# UV_lamp.net
KiCad netlist of a schematic drawn in EAGLE
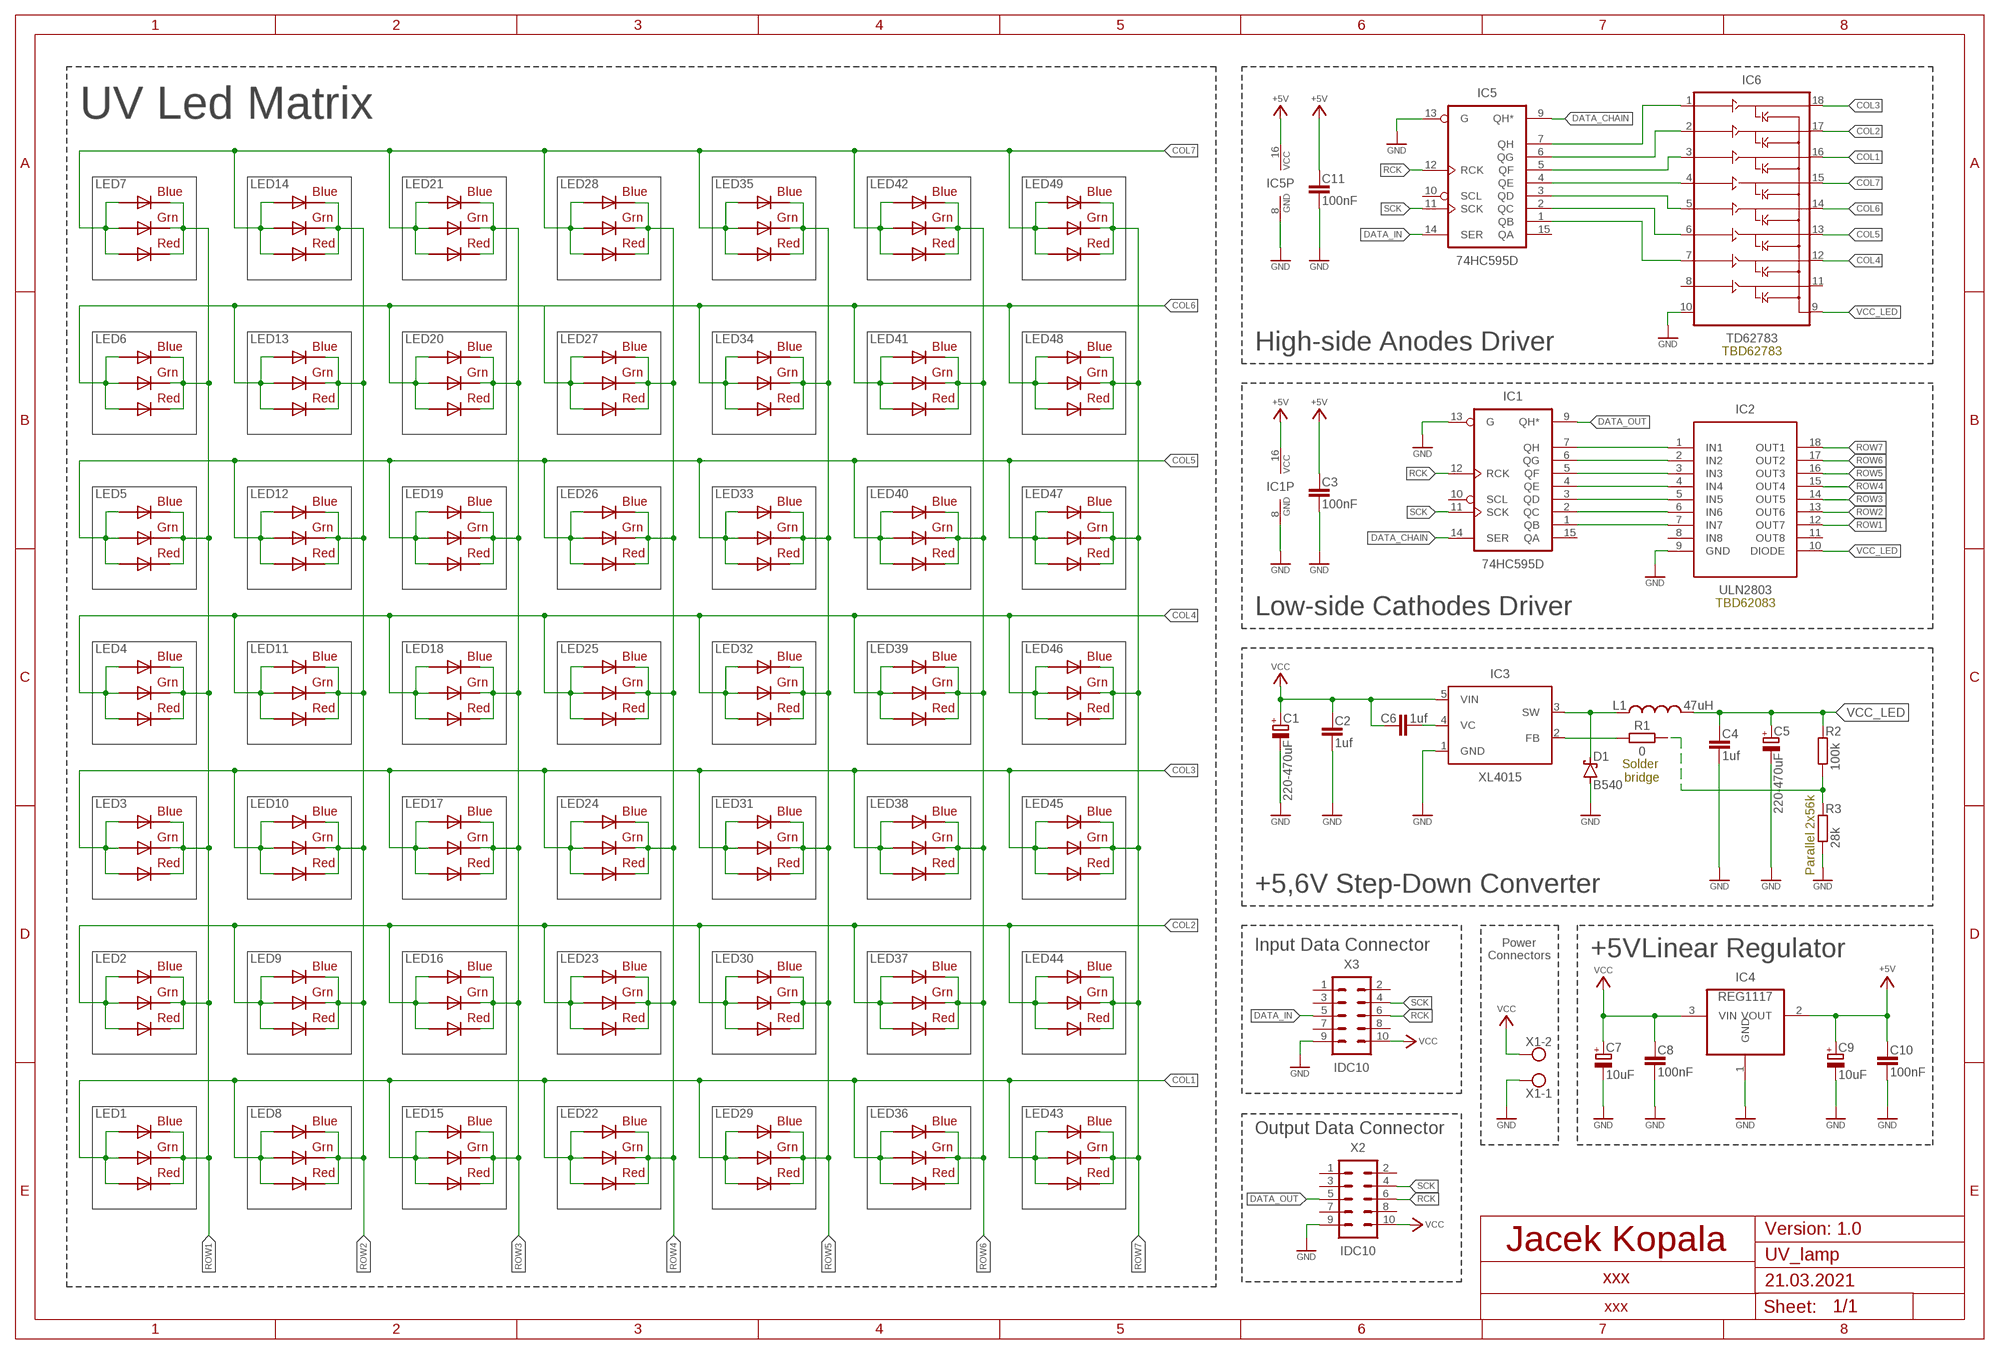
[diagram p0: schematic, sheet 1]

(export (version "E")
  (design (tool "Eeschema 10.0.6"))
  (components
    (comp (ref "C1")
      (value "220-470uF")
      (footprint "eagle-import:140CLH-1010")
      (libsource (lib "eagle-import") (part "CPOL-EU140CLH-1010"))
    )
    (comp (ref "C2")
      (value "1uf")
      (footprint "eagle-import:C0805")
      (fields (field (name "SPICEPREFIX") "C"))
      (libsource (lib "eagle-import") (part "C-EUC0805"))
    )
    (comp (ref "C3")
      (value "100nF")
      (footprint "eagle-import:C0805")
      (libsource (lib "eagle-import") (part "rcl_334_C-EUC0805"))
    )
    (comp (ref "C4")
      (value "1uf")
      (footprint "eagle-import:C0805")
      (fields (field (name "SPICEPREFIX") "C"))
      (libsource (lib "eagle-import") (part "C-EUC0805"))
    )
    (comp (ref "C5")
      (value "220-470uF")
      (footprint "eagle-import:140CLH-1010")
      (libsource (lib "eagle-import") (part "CPOL-EU140CLH-1010"))
    )
    (comp (ref "C6")
      (value "1uf")
      (footprint "eagle-import:C0805")
      (fields (field (name "SPICEPREFIX") "C"))
      (libsource (lib "eagle-import") (part "C-EUC0805"))
    )
    (comp (ref "C7")
      (value "10uF")
      (footprint "eagle-import:153CLV-0405")
      (libsource (lib "eagle-import") (part "CPOL-EU153CLV-0405"))
    )
    (comp (ref "C8")
      (value "100nF")
      (footprint "eagle-import:C0805")
      (fields (field (name "SPICEPREFIX") "C"))
      (libsource (lib "eagle-import") (part "C-EUC0805"))
    )
    (comp (ref "C9")
      (value "10uF")
      (footprint "eagle-import:153CLV-0405")
      (libsource (lib "eagle-import") (part "CPOL-EU153CLV-0405"))
    )
    (comp (ref "C10")
      (value "100nF")
      (footprint "eagle-import:C0805")
      (fields (field (name "SPICEPREFIX") "C"))
      (libsource (lib "eagle-import") (part "C-EUC0805"))
    )
    (comp (ref "C11")
      (value "100nF")
      (footprint "eagle-import:C0805")
      (libsource (lib "eagle-import") (part "rcl_334_C-EUC0805"))
    )
    (comp (ref "D1")
      (value "B540")
      (footprint "eagle-import:SMC")
      (libsource (lib "eagle-import") (part "MBRS30T34"))
    )
    (comp (ref "IC1")
      (value "74HC595D")
      (footprint "eagle-import:SO16")
      (libsource (lib "eagle-import") (part "74595DHC"))
    )
    (comp (ref "IC2")
      (value "ULN2803")
      (footprint "eagle-import:SO18L")
      (libsource (lib "eagle-import") (part "ULN2803"))
    )
    (comp (ref "IC3")
      (value "XL4015")
      (footprint "eagle-import:TO263-5")
      (libsource (lib "eagle-import") (part "XL4015"))
    )
    (comp (ref "IC4")
      (value "REG1117")
      (footprint "eagle-import:SOT223")
      (libsource (lib "eagle-import") (part "REG1117"))
    )
    (comp (ref "IC5")
      (value "74HC595D")
      (footprint "eagle-import:SO16")
      (libsource (lib "eagle-import") (part "74595DHC"))
    )
    (comp (ref "IC6")
      (value "TD62783")
      (footprint "eagle-import:SO-18L")
      (libsource (lib "eagle-import") (part "IC_TD62783-SO-18W"))
    )
    (comp (ref "L1")
      (value "47uH")
      (footprint "eagle-import:TJ5-U1")
      (libsource (lib "eagle-import") (part "L-USTJ5-U1"))
    )
    (comp (ref "LED1")
      (value "RGBLED5050")
      (footprint "eagle-import:RGBLED5050")
      (libsource (lib "eagle-import") (part "RGBLED5050"))
    )
    (comp (ref "LED2")
      (value "RGBLED5050")
      (footprint "eagle-import:RGBLED5050")
      (libsource (lib "eagle-import") (part "RGBLED5050"))
    )
    (comp (ref "LED3")
      (value "RGBLED5050")
      (footprint "eagle-import:RGBLED5050")
      (libsource (lib "eagle-import") (part "RGBLED5050"))
    )
    (comp (ref "LED4")
      (value "RGBLED5050")
      (footprint "eagle-import:RGBLED5050")
      (libsource (lib "eagle-import") (part "RGBLED5050"))
    )
    (comp (ref "LED5")
      (value "RGBLED5050")
      (footprint "eagle-import:RGBLED5050")
      (libsource (lib "eagle-import") (part "RGBLED5050"))
    )
    (comp (ref "LED6")
      (value "RGBLED5050")
      (footprint "eagle-import:RGBLED5050")
      (libsource (lib "eagle-import") (part "RGBLED5050"))
    )
    (comp (ref "LED7")
      (value "RGBLED5050")
      (footprint "eagle-import:RGBLED5050")
      (libsource (lib "eagle-import") (part "RGBLED5050"))
    )
    (comp (ref "LED8")
      (value "RGBLED5050")
      (footprint "eagle-import:RGBLED5050")
      (libsource (lib "eagle-import") (part "RGBLED5050"))
    )
    (comp (ref "LED9")
      (value "RGBLED5050")
      (footprint "eagle-import:RGBLED5050")
      (libsource (lib "eagle-import") (part "RGBLED5050"))
    )
    (comp (ref "LED10")
      (value "RGBLED5050")
      (footprint "eagle-import:RGBLED5050")
      (libsource (lib "eagle-import") (part "RGBLED5050"))
    )
    (comp (ref "LED11")
      (value "RGBLED5050")
      (footprint "eagle-import:RGBLED5050")
      (libsource (lib "eagle-import") (part "RGBLED5050"))
    )
    (comp (ref "LED12")
      (value "RGBLED5050")
      (footprint "eagle-import:RGBLED5050")
      (libsource (lib "eagle-import") (part "RGBLED5050"))
    )
    (comp (ref "LED13")
      (value "RGBLED5050")
      (footprint "eagle-import:RGBLED5050")
      (libsource (lib "eagle-import") (part "RGBLED5050"))
    )
    (comp (ref "LED14")
      (value "RGBLED5050")
      (footprint "eagle-import:RGBLED5050")
      (libsource (lib "eagle-import") (part "RGBLED5050"))
    )
    (comp (ref "LED15")
      (value "RGBLED5050")
      (footprint "eagle-import:RGBLED5050")
      (libsource (lib "eagle-import") (part "RGBLED5050"))
    )
    (comp (ref "LED16")
      (value "RGBLED5050")
      (footprint "eagle-import:RGBLED5050")
      (libsource (lib "eagle-import") (part "RGBLED5050"))
    )
    (comp (ref "LED17")
      (value "RGBLED5050")
      (footprint "eagle-import:RGBLED5050")
      (libsource (lib "eagle-import") (part "RGBLED5050"))
    )
    (comp (ref "LED18")
      (value "RGBLED5050")
      (footprint "eagle-import:RGBLED5050")
      (libsource (lib "eagle-import") (part "RGBLED5050"))
    )
    (comp (ref "LED19")
      (value "RGBLED5050")
      (footprint "eagle-import:RGBLED5050")
      (libsource (lib "eagle-import") (part "RGBLED5050"))
    )
    (comp (ref "LED20")
      (value "RGBLED5050")
      (footprint "eagle-import:RGBLED5050")
      (libsource (lib "eagle-import") (part "RGBLED5050"))
    )
    (comp (ref "LED21")
      (value "RGBLED5050")
      (footprint "eagle-import:RGBLED5050")
      (libsource (lib "eagle-import") (part "RGBLED5050"))
    )
    (comp (ref "LED22")
      (value "RGBLED5050")
      (footprint "eagle-import:RGBLED5050")
      (libsource (lib "eagle-import") (part "RGBLED5050"))
    )
    (comp (ref "LED23")
      (value "RGBLED5050")
      (footprint "eagle-import:RGBLED5050")
      (libsource (lib "eagle-import") (part "RGBLED5050"))
    )
    (comp (ref "LED24")
      (value "RGBLED5050")
      (footprint "eagle-import:RGBLED5050")
      (libsource (lib "eagle-import") (part "RGBLED5050"))
    )
    (comp (ref "LED25")
      (value "RGBLED5050")
      (footprint "eagle-import:RGBLED5050")
      (libsource (lib "eagle-import") (part "RGBLED5050"))
    )
    (comp (ref "LED26")
      (value "RGBLED5050")
      (footprint "eagle-import:RGBLED5050")
      (libsource (lib "eagle-import") (part "RGBLED5050"))
    )
    (comp (ref "LED27")
      (value "RGBLED5050")
      (footprint "eagle-import:RGBLED5050")
      (libsource (lib "eagle-import") (part "RGBLED5050"))
    )
    (comp (ref "LED28")
      (value "RGBLED5050")
      (footprint "eagle-import:RGBLED5050")
      (libsource (lib "eagle-import") (part "RGBLED5050"))
    )
    (comp (ref "LED29")
      (value "RGBLED5050")
      (footprint "eagle-import:RGBLED5050")
      (libsource (lib "eagle-import") (part "RGBLED5050"))
    )
    (comp (ref "LED30")
      (value "RGBLED5050")
      (footprint "eagle-import:RGBLED5050")
      (libsource (lib "eagle-import") (part "RGBLED5050"))
    )
    (comp (ref "LED31")
      (value "RGBLED5050")
      (footprint "eagle-import:RGBLED5050")
      (libsource (lib "eagle-import") (part "RGBLED5050"))
    )
    (comp (ref "LED32")
      (value "RGBLED5050")
      (footprint "eagle-import:RGBLED5050")
      (libsource (lib "eagle-import") (part "RGBLED5050"))
    )
    (comp (ref "LED33")
      (value "RGBLED5050")
      (footprint "eagle-import:RGBLED5050")
      (libsource (lib "eagle-import") (part "RGBLED5050"))
    )
    (comp (ref "LED34")
      (value "RGBLED5050")
      (footprint "eagle-import:RGBLED5050")
      (libsource (lib "eagle-import") (part "RGBLED5050"))
    )
    (comp (ref "LED35")
      (value "RGBLED5050")
      (footprint "eagle-import:RGBLED5050")
      (libsource (lib "eagle-import") (part "RGBLED5050"))
    )
    (comp (ref "LED36")
      (value "RGBLED5050")
      (footprint "eagle-import:RGBLED5050")
      (libsource (lib "eagle-import") (part "RGBLED5050"))
    )
    (comp (ref "LED37")
      (value "RGBLED5050")
      (footprint "eagle-import:RGBLED5050")
      (libsource (lib "eagle-import") (part "RGBLED5050"))
    )
    (comp (ref "LED38")
      (value "RGBLED5050")
      (footprint "eagle-import:RGBLED5050")
      (libsource (lib "eagle-import") (part "RGBLED5050"))
    )
    (comp (ref "LED39")
      (value "RGBLED5050")
      (footprint "eagle-import:RGBLED5050")
      (libsource (lib "eagle-import") (part "RGBLED5050"))
    )
    (comp (ref "LED40")
      (value "RGBLED5050")
      (footprint "eagle-import:RGBLED5050")
      (libsource (lib "eagle-import") (part "RGBLED5050"))
    )
    (comp (ref "LED41")
      (value "RGBLED5050")
      (footprint "eagle-import:RGBLED5050")
      (libsource (lib "eagle-import") (part "RGBLED5050"))
    )
    (comp (ref "LED42")
      (value "RGBLED5050")
      (footprint "eagle-import:RGBLED5050")
      (libsource (lib "eagle-import") (part "RGBLED5050"))
    )
    (comp (ref "LED43")
      (value "RGBLED5050")
      (footprint "eagle-import:RGBLED5050")
      (libsource (lib "eagle-import") (part "RGBLED5050"))
    )
    (comp (ref "LED44")
      (value "RGBLED5050")
      (footprint "eagle-import:RGBLED5050")
      (libsource (lib "eagle-import") (part "RGBLED5050"))
    )
    (comp (ref "LED45")
      (value "RGBLED5050")
      (footprint "eagle-import:RGBLED5050")
      (libsource (lib "eagle-import") (part "RGBLED5050"))
    )
    (comp (ref "LED46")
      (value "RGBLED5050")
      (footprint "eagle-import:RGBLED5050")
      (libsource (lib "eagle-import") (part "RGBLED5050"))
    )
    (comp (ref "LED47")
      (value "RGBLED5050")
      (footprint "eagle-import:RGBLED5050")
      (libsource (lib "eagle-import") (part "RGBLED5050"))
    )
    (comp (ref "LED48")
      (value "RGBLED5050")
      (footprint "eagle-import:RGBLED5050")
      (libsource (lib "eagle-import") (part "RGBLED5050"))
    )
    (comp (ref "LED49")
      (value "RGBLED5050")
      (footprint "eagle-import:RGBLED5050")
      (libsource (lib "eagle-import") (part "RGBLED5050"))
    )
    (comp (ref "R1")
      (value "0")
      (footprint "eagle-import:R0805")
      (libsource (lib "eagle-import") (part "R-EU_R0805"))
    )
    (comp (ref "R2")
      (value "100k")
      (footprint "eagle-import:R0805")
      (libsource (lib "eagle-import") (part "R-EU_R0805"))
    )
    (comp (ref "R3")
      (value "28k")
      (footprint "eagle-import:R0805")
      (libsource (lib "eagle-import") (part "R-EU_R0805"))
    )
    (comp (ref "X1")
      (value "AK500/2")
      (footprint "eagle-import:AK500_2")
      (libsource (lib "eagle-import") (part "AK500/2"))
    )
    (comp (ref "X2")
      (value "IDC10")
      (footprint "eagle-import:ML10")
      (libsource (lib "eagle-import") (part "IDC10"))
    )
    (comp (ref "X3")
      (value "IDC10")
      (footprint "eagle-import:ML10")
      (libsource (lib "eagle-import") (part "IDC10"))
    )
  )
  (nets
    (net (code "1") (name "+5V") (class "Default")
      (node (ref "C10") (pin "1") (pinfunction "1_1") (pintype "passive"))
      (node (ref "C11") (pin "1") (pinfunction "1_1") (pintype "passive"))
      (node (ref "C3") (pin "1") (pinfunction "1_1") (pintype "passive"))
      (node (ref "C9") (pin "+") (pinfunction "+_+") (pintype "passive"))
      (node (ref "IC1") (pin "16") (pinfunction "VCC_16") (pintype "power_in"))
      (node (ref "IC4") (pin "2") (pinfunction "VOUT_2") (pintype "output"))
      (node (ref "IC5") (pin "16") (pinfunction "VCC_16") (pintype "power_in"))
    )
    (net (code "2") (name "COL1") (class "Default")
      (node (ref "IC6") (pin "16") (pinfunction "OUT3_16") (pintype "output"))
      (node (ref "LED1") (pin "1") (pinfunction "GREEN_A_1") (pintype "bidirectional"))
      (node (ref "LED1") (pin "2") (pinfunction "RED_A_2") (pintype "bidirectional"))
      (node (ref "LED1") (pin "3") (pinfunction "BLUE_A_3") (pintype "bidirectional"))
      (node (ref "LED15") (pin "1") (pinfunction "GREEN_A_1") (pintype "bidirectional"))
      (node (ref "LED15") (pin "2") (pinfunction "RED_A_2") (pintype "bidirectional"))
      (node (ref "LED15") (pin "3") (pinfunction "BLUE_A_3") (pintype "bidirectional"))
      (node (ref "LED22") (pin "1") (pinfunction "GREEN_A_1") (pintype "bidirectional"))
      (node (ref "LED22") (pin "2") (pinfunction "RED_A_2") (pintype "bidirectional"))
      (node (ref "LED22") (pin "3") (pinfunction "BLUE_A_3") (pintype "bidirectional"))
      (node (ref "LED29") (pin "1") (pinfunction "GREEN_A_1") (pintype "bidirectional"))
      (node (ref "LED29") (pin "2") (pinfunction "RED_A_2") (pintype "bidirectional"))
      (node (ref "LED29") (pin "3") (pinfunction "BLUE_A_3") (pintype "bidirectional"))
      (node (ref "LED36") (pin "1") (pinfunction "GREEN_A_1") (pintype "bidirectional"))
      (node (ref "LED36") (pin "2") (pinfunction "RED_A_2") (pintype "bidirectional"))
      (node (ref "LED36") (pin "3") (pinfunction "BLUE_A_3") (pintype "bidirectional"))
      (node (ref "LED43") (pin "1") (pinfunction "GREEN_A_1") (pintype "bidirectional"))
      (node (ref "LED43") (pin "2") (pinfunction "RED_A_2") (pintype "bidirectional"))
      (node (ref "LED43") (pin "3") (pinfunction "BLUE_A_3") (pintype "bidirectional"))
      (node (ref "LED8") (pin "1") (pinfunction "GREEN_A_1") (pintype "bidirectional"))
      (node (ref "LED8") (pin "2") (pinfunction "RED_A_2") (pintype "bidirectional"))
      (node (ref "LED8") (pin "3") (pinfunction "BLUE_A_3") (pintype "bidirectional"))
    )
    (net (code "3") (name "COL2") (class "Default")
      (node (ref "IC6") (pin "17") (pinfunction "OUT2_17") (pintype "output"))
      (node (ref "LED16") (pin "1") (pinfunction "GREEN_A_1") (pintype "bidirectional"))
      (node (ref "LED16") (pin "2") (pinfunction "RED_A_2") (pintype "bidirectional"))
      (node (ref "LED16") (pin "3") (pinfunction "BLUE_A_3") (pintype "bidirectional"))
      (node (ref "LED2") (pin "1") (pinfunction "GREEN_A_1") (pintype "bidirectional"))
      (node (ref "LED2") (pin "2") (pinfunction "RED_A_2") (pintype "bidirectional"))
      (node (ref "LED2") (pin "3") (pinfunction "BLUE_A_3") (pintype "bidirectional"))
      (node (ref "LED23") (pin "1") (pinfunction "GREEN_A_1") (pintype "bidirectional"))
      (node (ref "LED23") (pin "2") (pinfunction "RED_A_2") (pintype "bidirectional"))
      (node (ref "LED23") (pin "3") (pinfunction "BLUE_A_3") (pintype "bidirectional"))
      (node (ref "LED30") (pin "1") (pinfunction "GREEN_A_1") (pintype "bidirectional"))
      (node (ref "LED30") (pin "2") (pinfunction "RED_A_2") (pintype "bidirectional"))
      (node (ref "LED30") (pin "3") (pinfunction "BLUE_A_3") (pintype "bidirectional"))
      (node (ref "LED37") (pin "1") (pinfunction "GREEN_A_1") (pintype "bidirectional"))
      (node (ref "LED37") (pin "2") (pinfunction "RED_A_2") (pintype "bidirectional"))
      (node (ref "LED37") (pin "3") (pinfunction "BLUE_A_3") (pintype "bidirectional"))
      (node (ref "LED44") (pin "1") (pinfunction "GREEN_A_1") (pintype "bidirectional"))
      (node (ref "LED44") (pin "2") (pinfunction "RED_A_2") (pintype "bidirectional"))
      (node (ref "LED44") (pin "3") (pinfunction "BLUE_A_3") (pintype "bidirectional"))
      (node (ref "LED9") (pin "1") (pinfunction "GREEN_A_1") (pintype "bidirectional"))
      (node (ref "LED9") (pin "2") (pinfunction "RED_A_2") (pintype "bidirectional"))
      (node (ref "LED9") (pin "3") (pinfunction "BLUE_A_3") (pintype "bidirectional"))
    )
    (net (code "4") (name "COL3") (class "Default")
      (node (ref "IC6") (pin "18") (pinfunction "OUT1_18") (pintype "output"))
      (node (ref "LED10") (pin "1") (pinfunction "GREEN_A_1") (pintype "bidirectional"))
      (node (ref "LED10") (pin "2") (pinfunction "RED_A_2") (pintype "bidirectional"))
      (node (ref "LED10") (pin "3") (pinfunction "BLUE_A_3") (pintype "bidirectional"))
      (node (ref "LED17") (pin "1") (pinfunction "GREEN_A_1") (pintype "bidirectional"))
      (node (ref "LED17") (pin "2") (pinfunction "RED_A_2") (pintype "bidirectional"))
      (node (ref "LED17") (pin "3") (pinfunction "BLUE_A_3") (pintype "bidirectional"))
      (node (ref "LED24") (pin "1") (pinfunction "GREEN_A_1") (pintype "bidirectional"))
      (node (ref "LED24") (pin "2") (pinfunction "RED_A_2") (pintype "bidirectional"))
      (node (ref "LED24") (pin "3") (pinfunction "BLUE_A_3") (pintype "bidirectional"))
      (node (ref "LED3") (pin "1") (pinfunction "GREEN_A_1") (pintype "bidirectional"))
      (node (ref "LED3") (pin "2") (pinfunction "RED_A_2") (pintype "bidirectional"))
      (node (ref "LED3") (pin "3") (pinfunction "BLUE_A_3") (pintype "bidirectional"))
      (node (ref "LED31") (pin "1") (pinfunction "GREEN_A_1") (pintype "bidirectional"))
      (node (ref "LED31") (pin "2") (pinfunction "RED_A_2") (pintype "bidirectional"))
      (node (ref "LED31") (pin "3") (pinfunction "BLUE_A_3") (pintype "bidirectional"))
      (node (ref "LED38") (pin "1") (pinfunction "GREEN_A_1") (pintype "bidirectional"))
      (node (ref "LED38") (pin "2") (pinfunction "RED_A_2") (pintype "bidirectional"))
      (node (ref "LED38") (pin "3") (pinfunction "BLUE_A_3") (pintype "bidirectional"))
      (node (ref "LED45") (pin "1") (pinfunction "GREEN_A_1") (pintype "bidirectional"))
      (node (ref "LED45") (pin "2") (pinfunction "RED_A_2") (pintype "bidirectional"))
      (node (ref "LED45") (pin "3") (pinfunction "BLUE_A_3") (pintype "bidirectional"))
    )
    (net (code "5") (name "COL4") (class "Default")
      (node (ref "IC6") (pin "12") (pinfunction "OUT7_12") (pintype "output"))
      (node (ref "LED11") (pin "1") (pinfunction "GREEN_A_1") (pintype "bidirectional"))
      (node (ref "LED11") (pin "2") (pinfunction "RED_A_2") (pintype "bidirectional"))
      (node (ref "LED11") (pin "3") (pinfunction "BLUE_A_3") (pintype "bidirectional"))
      (node (ref "LED18") (pin "1") (pinfunction "GREEN_A_1") (pintype "bidirectional"))
      (node (ref "LED18") (pin "2") (pinfunction "RED_A_2") (pintype "bidirectional"))
      (node (ref "LED18") (pin "3") (pinfunction "BLUE_A_3") (pintype "bidirectional"))
      (node (ref "LED25") (pin "1") (pinfunction "GREEN_A_1") (pintype "bidirectional"))
      (node (ref "LED25") (pin "2") (pinfunction "RED_A_2") (pintype "bidirectional"))
      (node (ref "LED25") (pin "3") (pinfunction "BLUE_A_3") (pintype "bidirectional"))
      (node (ref "LED32") (pin "1") (pinfunction "GREEN_A_1") (pintype "bidirectional"))
      (node (ref "LED32") (pin "2") (pinfunction "RED_A_2") (pintype "bidirectional"))
      (node (ref "LED32") (pin "3") (pinfunction "BLUE_A_3") (pintype "bidirectional"))
      (node (ref "LED39") (pin "1") (pinfunction "GREEN_A_1") (pintype "bidirectional"))
      (node (ref "LED39") (pin "2") (pinfunction "RED_A_2") (pintype "bidirectional"))
      (node (ref "LED39") (pin "3") (pinfunction "BLUE_A_3") (pintype "bidirectional"))
      (node (ref "LED4") (pin "1") (pinfunction "GREEN_A_1") (pintype "bidirectional"))
      (node (ref "LED4") (pin "2") (pinfunction "RED_A_2") (pintype "bidirectional"))
      (node (ref "LED4") (pin "3") (pinfunction "BLUE_A_3") (pintype "bidirectional"))
      (node (ref "LED46") (pin "1") (pinfunction "GREEN_A_1") (pintype "bidirectional"))
      (node (ref "LED46") (pin "2") (pinfunction "RED_A_2") (pintype "bidirectional"))
      (node (ref "LED46") (pin "3") (pinfunction "BLUE_A_3") (pintype "bidirectional"))
    )
    (net (code "6") (name "COL5") (class "Default")
      (node (ref "IC6") (pin "13") (pinfunction "OUT6_13") (pintype "output"))
      (node (ref "LED12") (pin "1") (pinfunction "GREEN_A_1") (pintype "bidirectional"))
      (node (ref "LED12") (pin "2") (pinfunction "RED_A_2") (pintype "bidirectional"))
      (node (ref "LED12") (pin "3") (pinfunction "BLUE_A_3") (pintype "bidirectional"))
      (node (ref "LED19") (pin "1") (pinfunction "GREEN_A_1") (pintype "bidirectional"))
      (node (ref "LED19") (pin "2") (pinfunction "RED_A_2") (pintype "bidirectional"))
      (node (ref "LED19") (pin "3") (pinfunction "BLUE_A_3") (pintype "bidirectional"))
      (node (ref "LED26") (pin "1") (pinfunction "GREEN_A_1") (pintype "bidirectional"))
      (node (ref "LED26") (pin "2") (pinfunction "RED_A_2") (pintype "bidirectional"))
      (node (ref "LED26") (pin "3") (pinfunction "BLUE_A_3") (pintype "bidirectional"))
      (node (ref "LED33") (pin "1") (pinfunction "GREEN_A_1") (pintype "bidirectional"))
      (node (ref "LED33") (pin "2") (pinfunction "RED_A_2") (pintype "bidirectional"))
      (node (ref "LED33") (pin "3") (pinfunction "BLUE_A_3") (pintype "bidirectional"))
      (node (ref "LED40") (pin "1") (pinfunction "GREEN_A_1") (pintype "bidirectional"))
      (node (ref "LED40") (pin "2") (pinfunction "RED_A_2") (pintype "bidirectional"))
      (node (ref "LED40") (pin "3") (pinfunction "BLUE_A_3") (pintype "bidirectional"))
      (node (ref "LED47") (pin "1") (pinfunction "GREEN_A_1") (pintype "bidirectional"))
      (node (ref "LED47") (pin "2") (pinfunction "RED_A_2") (pintype "bidirectional"))
      (node (ref "LED47") (pin "3") (pinfunction "BLUE_A_3") (pintype "bidirectional"))
      (node (ref "LED5") (pin "1") (pinfunction "GREEN_A_1") (pintype "bidirectional"))
      (node (ref "LED5") (pin "2") (pinfunction "RED_A_2") (pintype "bidirectional"))
      (node (ref "LED5") (pin "3") (pinfunction "BLUE_A_3") (pintype "bidirectional"))
    )
    (net (code "7") (name "COL6") (class "Default")
      (node (ref "IC6") (pin "14") (pinfunction "OUT5_14") (pintype "output"))
      (node (ref "LED13") (pin "1") (pinfunction "GREEN_A_1") (pintype "bidirectional"))
      (node (ref "LED13") (pin "2") (pinfunction "RED_A_2") (pintype "bidirectional"))
      (node (ref "LED13") (pin "3") (pinfunction "BLUE_A_3") (pintype "bidirectional"))
      (node (ref "LED20") (pin "1") (pinfunction "GREEN_A_1") (pintype "bidirectional"))
      (node (ref "LED20") (pin "2") (pinfunction "RED_A_2") (pintype "bidirectional"))
      (node (ref "LED20") (pin "3") (pinfunction "BLUE_A_3") (pintype "bidirectional"))
      (node (ref "LED27") (pin "1") (pinfunction "GREEN_A_1") (pintype "bidirectional"))
      (node (ref "LED27") (pin "2") (pinfunction "RED_A_2") (pintype "bidirectional"))
      (node (ref "LED27") (pin "3") (pinfunction "BLUE_A_3") (pintype "bidirectional"))
      (node (ref "LED34") (pin "1") (pinfunction "GREEN_A_1") (pintype "bidirectional"))
      (node (ref "LED34") (pin "2") (pinfunction "RED_A_2") (pintype "bidirectional"))
      (node (ref "LED34") (pin "3") (pinfunction "BLUE_A_3") (pintype "bidirectional"))
      (node (ref "LED41") (pin "1") (pinfunction "GREEN_A_1") (pintype "bidirectional"))
      (node (ref "LED41") (pin "2") (pinfunction "RED_A_2") (pintype "bidirectional"))
      (node (ref "LED41") (pin "3") (pinfunction "BLUE_A_3") (pintype "bidirectional"))
      (node (ref "LED48") (pin "1") (pinfunction "GREEN_A_1") (pintype "bidirectional"))
      (node (ref "LED48") (pin "2") (pinfunction "RED_A_2") (pintype "bidirectional"))
      (node (ref "LED48") (pin "3") (pinfunction "BLUE_A_3") (pintype "bidirectional"))
      (node (ref "LED6") (pin "1") (pinfunction "GREEN_A_1") (pintype "bidirectional"))
      (node (ref "LED6") (pin "2") (pinfunction "RED_A_2") (pintype "bidirectional"))
      (node (ref "LED6") (pin "3") (pinfunction "BLUE_A_3") (pintype "bidirectional"))
    )
    (net (code "8") (name "COL7") (class "Default")
      (node (ref "IC6") (pin "15") (pinfunction "OUT4_15") (pintype "output"))
      (node (ref "LED14") (pin "1") (pinfunction "GREEN_A_1") (pintype "bidirectional"))
      (node (ref "LED14") (pin "2") (pinfunction "RED_A_2") (pintype "bidirectional"))
      (node (ref "LED14") (pin "3") (pinfunction "BLUE_A_3") (pintype "bidirectional"))
      (node (ref "LED21") (pin "1") (pinfunction "GREEN_A_1") (pintype "bidirectional"))
      (node (ref "LED21") (pin "2") (pinfunction "RED_A_2") (pintype "bidirectional"))
      (node (ref "LED21") (pin "3") (pinfunction "BLUE_A_3") (pintype "bidirectional"))
      (node (ref "LED28") (pin "1") (pinfunction "GREEN_A_1") (pintype "bidirectional"))
      (node (ref "LED28") (pin "2") (pinfunction "RED_A_2") (pintype "bidirectional"))
      (node (ref "LED28") (pin "3") (pinfunction "BLUE_A_3") (pintype "bidirectional"))
      (node (ref "LED35") (pin "1") (pinfunction "GREEN_A_1") (pintype "bidirectional"))
      (node (ref "LED35") (pin "2") (pinfunction "RED_A_2") (pintype "bidirectional"))
      (node (ref "LED35") (pin "3") (pinfunction "BLUE_A_3") (pintype "bidirectional"))
      (node (ref "LED42") (pin "1") (pinfunction "GREEN_A_1") (pintype "bidirectional"))
      (node (ref "LED42") (pin "2") (pinfunction "RED_A_2") (pintype "bidirectional"))
      (node (ref "LED42") (pin "3") (pinfunction "BLUE_A_3") (pintype "bidirectional"))
      (node (ref "LED49") (pin "1") (pinfunction "GREEN_A_1") (pintype "bidirectional"))
      (node (ref "LED49") (pin "2") (pinfunction "RED_A_2") (pintype "bidirectional"))
      (node (ref "LED49") (pin "3") (pinfunction "BLUE_A_3") (pintype "bidirectional"))
      (node (ref "LED7") (pin "1") (pinfunction "GREEN_A_1") (pintype "bidirectional"))
      (node (ref "LED7") (pin "2") (pinfunction "RED_A_2") (pintype "bidirectional"))
      (node (ref "LED7") (pin "3") (pinfunction "BLUE_A_3") (pintype "bidirectional"))
    )
    (net (code "9") (name "DATA_CHAIN") (class "Default")
      (node (ref "IC1") (pin "14") (pinfunction "SER_14") (pintype "input"))
      (node (ref "IC5") (pin "9") (pinfunction "QH*_9") (pintype "tri_state"))
    )
    (net (code "10") (name "DATA_IN") (class "Default")
      (node (ref "IC5") (pin "14") (pinfunction "SER_14") (pintype "input"))
      (node (ref "X3") (pin "5") (pinfunction "5_5") (pintype "passive"))
    )
    (net (code "11") (name "DATA_OUT") (class "Default")
      (node (ref "IC1") (pin "9") (pinfunction "QH*_9") (pintype "tri_state"))
      (node (ref "X2") (pin "5") (pinfunction "5_5") (pintype "passive"))
    )
    (net (code "12") (name "GND") (class "Default")
      (node (ref "C1") (pin "-") (pinfunction "-_-") (pintype "passive"))
      (node (ref "C10") (pin "2") (pinfunction "2_2") (pintype "passive"))
      (node (ref "C11") (pin "2") (pinfunction "2_2") (pintype "passive"))
      (node (ref "C2") (pin "2") (pinfunction "2_2") (pintype "passive"))
      (node (ref "C3") (pin "2") (pinfunction "2_2") (pintype "passive"))
      (node (ref "C4") (pin "2") (pinfunction "2_2") (pintype "passive"))
      (node (ref "C5") (pin "-") (pinfunction "-_-") (pintype "passive"))
      (node (ref "C7") (pin "-") (pinfunction "-_-") (pintype "passive"))
      (node (ref "C8") (pin "2") (pinfunction "2_2") (pintype "passive"))
      (node (ref "C9") (pin "-") (pinfunction "-_-") (pintype "passive"))
      (node (ref "D1") (pin "A") (pinfunction "A_A") (pintype "passive"))
      (node (ref "IC1") (pin "13") (pinfunction "G_13") (pintype "input"))
      (node (ref "IC1") (pin "8") (pinfunction "GND_8") (pintype "power_in"))
      (node (ref "IC2") (pin "9") (pinfunction "GND_9") (pintype "power_in"))
      (node (ref "IC3") (pin "1") (pinfunction "GND_1") (pintype "power_in"))
      (node (ref "IC4") (pin "1") (pinfunction "GND_1") (pintype "power_in"))
      (node (ref "IC5") (pin "13") (pinfunction "G_13") (pintype "input"))
      (node (ref "IC5") (pin "8") (pinfunction "GND_8") (pintype "power_in"))
      (node (ref "IC6") (pin "10") (pinfunction "VS_10") (pintype "power_in"))
      (node (ref "R3") (pin "1") (pinfunction "1_1") (pintype "passive"))
      (node (ref "X1") (pin "1") (pinfunction "KL_1") (pintype "passive"))
      (node (ref "X2") (pin "9") (pinfunction "9_9") (pintype "passive"))
      (node (ref "X3") (pin "9") (pinfunction "9_9") (pintype "passive"))
    )
    (net (code "13") (name "Net-(IC1A-QB)") (class "Default")
      (node (ref "IC1") (pin "1") (pinfunction "QB_1") (pintype "tri_state"))
      (node (ref "IC2") (pin "7") (pinfunction "IN7_7") (pintype "input"))
    )
    (net (code "14") (name "Net-(IC1A-QC)") (class "Default")
      (node (ref "IC1") (pin "2") (pinfunction "QC_2") (pintype "tri_state"))
      (node (ref "IC2") (pin "6") (pinfunction "IN6_6") (pintype "input"))
    )
    (net (code "15") (name "Net-(IC1A-QD)") (class "Default")
      (node (ref "IC1") (pin "3") (pinfunction "QD_3") (pintype "tri_state"))
      (node (ref "IC2") (pin "5") (pinfunction "IN5_5") (pintype "input"))
    )
    (net (code "16") (name "Net-(IC1A-QE)") (class "Default")
      (node (ref "IC1") (pin "4") (pinfunction "QE_4") (pintype "tri_state"))
      (node (ref "IC2") (pin "4") (pinfunction "IN4_4") (pintype "input"))
    )
    (net (code "17") (name "Net-(IC1A-QF)") (class "Default")
      (node (ref "IC1") (pin "5") (pinfunction "QF_5") (pintype "tri_state"))
      (node (ref "IC2") (pin "3") (pinfunction "IN3_3") (pintype "input"))
    )
    (net (code "18") (name "Net-(IC1A-QG)") (class "Default")
      (node (ref "IC1") (pin "6") (pinfunction "QG_6") (pintype "tri_state"))
      (node (ref "IC2") (pin "2") (pinfunction "IN2_2") (pintype "input"))
    )
    (net (code "19") (name "Net-(IC1A-QH)") (class "Default")
      (node (ref "IC1") (pin "7") (pinfunction "QH_7") (pintype "tri_state"))
      (node (ref "IC2") (pin "1") (pinfunction "IN1_1") (pintype "input"))
    )
    (net (code "20") (name "Net-(IC3-FB)") (class "Default")
      (node (ref "IC3") (pin "2") (pinfunction "FB_2") (pintype "input"))
      (node (ref "R1") (pin "2") (pinfunction "2_2") (pintype "passive"))
    )
    (net (code "21") (name "Net-(IC3-SW)") (class "Default")
      (node (ref "D1") (pin "C") (pinfunction "C_C") (pintype "passive"))
      (node (ref "IC3") (pin "3") (pinfunction "SW_3") (pintype "output"))
      (node (ref "L1") (pin "1") (pinfunction "1_1") (pintype "passive"))
    )
    (net (code "22") (name "Net-(IC3-VC)") (class "Default")
      (node (ref "C6") (pin "1") (pinfunction "1_1") (pintype "passive"))
      (node (ref "IC3") (pin "4") (pinfunction "VC_4") (pintype "input"))
    )
    (net (code "23") (name "Net-(IC5A-QB)") (class "Default")
      (node (ref "IC5") (pin "1") (pinfunction "QB_1") (pintype "tri_state"))
      (node (ref "IC6") (pin "7") (pinfunction "IN7_7") (pintype "input"))
    )
    (net (code "24") (name "Net-(IC5A-QC)") (class "Default")
      (node (ref "IC5") (pin "2") (pinfunction "QC_2") (pintype "tri_state"))
      (node (ref "IC6") (pin "6") (pinfunction "IN6_6") (pintype "input"))
    )
    (net (code "25") (name "Net-(IC5A-QD)") (class "Default")
      (node (ref "IC5") (pin "3") (pinfunction "QD_3") (pintype "tri_state"))
      (node (ref "IC6") (pin "5") (pinfunction "IN5_5") (pintype "input"))
    )
    (net (code "26") (name "Net-(IC5A-QE)") (class "Default")
      (node (ref "IC5") (pin "4") (pinfunction "QE_4") (pintype "tri_state"))
      (node (ref "IC6") (pin "4") (pinfunction "IN4_4") (pintype "input"))
    )
    (net (code "27") (name "Net-(IC5A-QF)") (class "Default")
      (node (ref "IC5") (pin "5") (pinfunction "QF_5") (pintype "tri_state"))
      (node (ref "IC6") (pin "3") (pinfunction "IN3_3") (pintype "input"))
    )
    (net (code "28") (name "Net-(IC5A-QG)") (class "Default")
      (node (ref "IC5") (pin "6") (pinfunction "QG_6") (pintype "tri_state"))
      (node (ref "IC6") (pin "2") (pinfunction "IN2_2") (pintype "input"))
    )
    (net (code "29") (name "Net-(IC5A-QH)") (class "Default")
      (node (ref "IC5") (pin "7") (pinfunction "QH_7") (pintype "tri_state"))
      (node (ref "IC6") (pin "1") (pinfunction "IN1_1") (pintype "input"))
    )
    (net (code "30") (name "Net-(R1-Pad1)") (class "Default")
      (node (ref "R1") (pin "1") (pinfunction "1_1") (pintype "passive"))
      (node (ref "R2") (pin "1") (pinfunction "1_1") (pintype "passive"))
      (node (ref "R3") (pin "2") (pinfunction "2_2") (pintype "passive"))
    )
    (net (code "31") (name "RCK") (class "Default")
      (node (ref "IC1") (pin "12") (pinfunction "RCK_12") (pintype "input"))
      (node (ref "IC5") (pin "12") (pinfunction "RCK_12") (pintype "input"))
      (node (ref "X2") (pin "6") (pinfunction "6_6") (pintype "passive"))
      (node (ref "X3") (pin "6") (pinfunction "6_6") (pintype "passive"))
    )
    (net (code "32") (name "ROW1") (class "Default")
      (node (ref "IC2") (pin "12") (pinfunction "OUT7_12") (pintype "open_collector"))
      (node (ref "LED1") (pin "4") (pinfunction "BLUE_C_4") (pintype "bidirectional"))
      (node (ref "LED1") (pin "5") (pinfunction "RED_C_5") (pintype "bidirectional"))
      (node (ref "LED1") (pin "6") (pinfunction "GREEN_C_6") (pintype "bidirectional"))
      (node (ref "LED2") (pin "4") (pinfunction "BLUE_C_4") (pintype "bidirectional"))
      (node (ref "LED2") (pin "5") (pinfunction "RED_C_5") (pintype "bidirectional"))
      (node (ref "LED2") (pin "6") (pinfunction "GREEN_C_6") (pintype "bidirectional"))
      (node (ref "LED3") (pin "4") (pinfunction "BLUE_C_4") (pintype "bidirectional"))
      (node (ref "LED3") (pin "5") (pinfunction "RED_C_5") (pintype "bidirectional"))
      (node (ref "LED3") (pin "6") (pinfunction "GREEN_C_6") (pintype "bidirectional"))
      (node (ref "LED4") (pin "4") (pinfunction "BLUE_C_4") (pintype "bidirectional"))
      (node (ref "LED4") (pin "5") (pinfunction "RED_C_5") (pintype "bidirectional"))
      (node (ref "LED4") (pin "6") (pinfunction "GREEN_C_6") (pintype "bidirectional"))
      (node (ref "LED5") (pin "4") (pinfunction "BLUE_C_4") (pintype "bidirectional"))
      (node (ref "LED5") (pin "5") (pinfunction "RED_C_5") (pintype "bidirectional"))
      (node (ref "LED5") (pin "6") (pinfunction "GREEN_C_6") (pintype "bidirectional"))
      (node (ref "LED6") (pin "4") (pinfunction "BLUE_C_4") (pintype "bidirectional"))
      (node (ref "LED6") (pin "5") (pinfunction "RED_C_5") (pintype "bidirectional"))
      (node (ref "LED6") (pin "6") (pinfunction "GREEN_C_6") (pintype "bidirectional"))
      (node (ref "LED7") (pin "4") (pinfunction "BLUE_C_4") (pintype "bidirectional"))
      (node (ref "LED7") (pin "5") (pinfunction "RED_C_5") (pintype "bidirectional"))
      (node (ref "LED7") (pin "6") (pinfunction "GREEN_C_6") (pintype "bidirectional"))
    )
    (net (code "33") (name "ROW2") (class "Default")
      (node (ref "IC2") (pin "13") (pinfunction "OUT6_13") (pintype "open_collector"))
      (node (ref "LED10") (pin "4") (pinfunction "BLUE_C_4") (pintype "bidirectional"))
      (node (ref "LED10") (pin "5") (pinfunction "RED_C_5") (pintype "bidirectional"))
      (node (ref "LED10") (pin "6") (pinfunction "GREEN_C_6") (pintype "bidirectional"))
      (node (ref "LED11") (pin "4") (pinfunction "BLUE_C_4") (pintype "bidirectional"))
      (node (ref "LED11") (pin "5") (pinfunction "RED_C_5") (pintype "bidirectional"))
      (node (ref "LED11") (pin "6") (pinfunction "GREEN_C_6") (pintype "bidirectional"))
      (node (ref "LED12") (pin "4") (pinfunction "BLUE_C_4") (pintype "bidirectional"))
      (node (ref "LED12") (pin "5") (pinfunction "RED_C_5") (pintype "bidirectional"))
      (node (ref "LED12") (pin "6") (pinfunction "GREEN_C_6") (pintype "bidirectional"))
      (node (ref "LED13") (pin "4") (pinfunction "BLUE_C_4") (pintype "bidirectional"))
      (node (ref "LED13") (pin "5") (pinfunction "RED_C_5") (pintype "bidirectional"))
      (node (ref "LED13") (pin "6") (pinfunction "GREEN_C_6") (pintype "bidirectional"))
      (node (ref "LED14") (pin "4") (pinfunction "BLUE_C_4") (pintype "bidirectional"))
      (node (ref "LED14") (pin "5") (pinfunction "RED_C_5") (pintype "bidirectional"))
      (node (ref "LED14") (pin "6") (pinfunction "GREEN_C_6") (pintype "bidirectional"))
      (node (ref "LED8") (pin "4") (pinfunction "BLUE_C_4") (pintype "bidirectional"))
      (node (ref "LED8") (pin "5") (pinfunction "RED_C_5") (pintype "bidirectional"))
      (node (ref "LED8") (pin "6") (pinfunction "GREEN_C_6") (pintype "bidirectional"))
      (node (ref "LED9") (pin "4") (pinfunction "BLUE_C_4") (pintype "bidirectional"))
      (node (ref "LED9") (pin "5") (pinfunction "RED_C_5") (pintype "bidirectional"))
      (node (ref "LED9") (pin "6") (pinfunction "GREEN_C_6") (pintype "bidirectional"))
    )
    (net (code "34") (name "ROW3") (class "Default")
      (node (ref "IC2") (pin "14") (pinfunction "OUT5_14") (pintype "open_collector"))
      (node (ref "LED15") (pin "4") (pinfunction "BLUE_C_4") (pintype "bidirectional"))
      (node (ref "LED15") (pin "5") (pinfunction "RED_C_5") (pintype "bidirectional"))
      (node (ref "LED15") (pin "6") (pinfunction "GREEN_C_6") (pintype "bidirectional"))
      (node (ref "LED16") (pin "4") (pinfunction "BLUE_C_4") (pintype "bidirectional"))
      (node (ref "LED16") (pin "5") (pinfunction "RED_C_5") (pintype "bidirectional"))
      (node (ref "LED16") (pin "6") (pinfunction "GREEN_C_6") (pintype "bidirectional"))
      (node (ref "LED17") (pin "4") (pinfunction "BLUE_C_4") (pintype "bidirectional"))
      (node (ref "LED17") (pin "5") (pinfunction "RED_C_5") (pintype "bidirectional"))
      (node (ref "LED17") (pin "6") (pinfunction "GREEN_C_6") (pintype "bidirectional"))
      (node (ref "LED18") (pin "4") (pinfunction "BLUE_C_4") (pintype "bidirectional"))
      (node (ref "LED18") (pin "5") (pinfunction "RED_C_5") (pintype "bidirectional"))
      (node (ref "LED18") (pin "6") (pinfunction "GREEN_C_6") (pintype "bidirectional"))
      (node (ref "LED19") (pin "4") (pinfunction "BLUE_C_4") (pintype "bidirectional"))
      (node (ref "LED19") (pin "5") (pinfunction "RED_C_5") (pintype "bidirectional"))
      (node (ref "LED19") (pin "6") (pinfunction "GREEN_C_6") (pintype "bidirectional"))
      (node (ref "LED20") (pin "4") (pinfunction "BLUE_C_4") (pintype "bidirectional"))
      (node (ref "LED20") (pin "5") (pinfunction "RED_C_5") (pintype "bidirectional"))
      (node (ref "LED20") (pin "6") (pinfunction "GREEN_C_6") (pintype "bidirectional"))
      (node (ref "LED21") (pin "4") (pinfunction "BLUE_C_4") (pintype "bidirectional"))
      (node (ref "LED21") (pin "5") (pinfunction "RED_C_5") (pintype "bidirectional"))
      (node (ref "LED21") (pin "6") (pinfunction "GREEN_C_6") (pintype "bidirectional"))
    )
    (net (code "35") (name "ROW4") (class "Default")
      (node (ref "IC2") (pin "15") (pinfunction "OUT4_15") (pintype "open_collector"))
      (node (ref "LED22") (pin "4") (pinfunction "BLUE_C_4") (pintype "bidirectional"))
      (node (ref "LED22") (pin "5") (pinfunction "RED_C_5") (pintype "bidirectional"))
      (node (ref "LED22") (pin "6") (pinfunction "GREEN_C_6") (pintype "bidirectional"))
      (node (ref "LED23") (pin "4") (pinfunction "BLUE_C_4") (pintype "bidirectional"))
      (node (ref "LED23") (pin "5") (pinfunction "RED_C_5") (pintype "bidirectional"))
      (node (ref "LED23") (pin "6") (pinfunction "GREEN_C_6") (pintype "bidirectional"))
      (node (ref "LED24") (pin "4") (pinfunction "BLUE_C_4") (pintype "bidirectional"))
      (node (ref "LED24") (pin "5") (pinfunction "RED_C_5") (pintype "bidirectional"))
      (node (ref "LED24") (pin "6") (pinfunction "GREEN_C_6") (pintype "bidirectional"))
      (node (ref "LED25") (pin "4") (pinfunction "BLUE_C_4") (pintype "bidirectional"))
      (node (ref "LED25") (pin "5") (pinfunction "RED_C_5") (pintype "bidirectional"))
      (node (ref "LED25") (pin "6") (pinfunction "GREEN_C_6") (pintype "bidirectional"))
      (node (ref "LED26") (pin "4") (pinfunction "BLUE_C_4") (pintype "bidirectional"))
      (node (ref "LED26") (pin "5") (pinfunction "RED_C_5") (pintype "bidirectional"))
      (node (ref "LED26") (pin "6") (pinfunction "GREEN_C_6") (pintype "bidirectional"))
      (node (ref "LED27") (pin "4") (pinfunction "BLUE_C_4") (pintype "bidirectional"))
      (node (ref "LED27") (pin "5") (pinfunction "RED_C_5") (pintype "bidirectional"))
      (node (ref "LED27") (pin "6") (pinfunction "GREEN_C_6") (pintype "bidirectional"))
      (node (ref "LED28") (pin "4") (pinfunction "BLUE_C_4") (pintype "bidirectional"))
      (node (ref "LED28") (pin "5") (pinfunction "RED_C_5") (pintype "bidirectional"))
      (node (ref "LED28") (pin "6") (pinfunction "GREEN_C_6") (pintype "bidirectional"))
    )
    (net (code "36") (name "ROW5") (class "Default")
      (node (ref "IC2") (pin "16") (pinfunction "OUT3_16") (pintype "open_collector"))
      (node (ref "LED29") (pin "4") (pinfunction "BLUE_C_4") (pintype "bidirectional"))
      (node (ref "LED29") (pin "5") (pinfunction "RED_C_5") (pintype "bidirectional"))
      (node (ref "LED29") (pin "6") (pinfunction "GREEN_C_6") (pintype "bidirectional"))
      (node (ref "LED30") (pin "4") (pinfunction "BLUE_C_4") (pintype "bidirectional"))
      (node (ref "LED30") (pin "5") (pinfunction "RED_C_5") (pintype "bidirectional"))
      (node (ref "LED30") (pin "6") (pinfunction "GREEN_C_6") (pintype "bidirectional"))
      (node (ref "LED31") (pin "4") (pinfunction "BLUE_C_4") (pintype "bidirectional"))
      (node (ref "LED31") (pin "5") (pinfunction "RED_C_5") (pintype "bidirectional"))
      (node (ref "LED31") (pin "6") (pinfunction "GREEN_C_6") (pintype "bidirectional"))
      (node (ref "LED32") (pin "4") (pinfunction "BLUE_C_4") (pintype "bidirectional"))
      (node (ref "LED32") (pin "5") (pinfunction "RED_C_5") (pintype "bidirectional"))
      (node (ref "LED32") (pin "6") (pinfunction "GREEN_C_6") (pintype "bidirectional"))
      (node (ref "LED33") (pin "4") (pinfunction "BLUE_C_4") (pintype "bidirectional"))
      (node (ref "LED33") (pin "5") (pinfunction "RED_C_5") (pintype "bidirectional"))
      (node (ref "LED33") (pin "6") (pinfunction "GREEN_C_6") (pintype "bidirectional"))
      (node (ref "LED34") (pin "4") (pinfunction "BLUE_C_4") (pintype "bidirectional"))
      (node (ref "LED34") (pin "5") (pinfunction "RED_C_5") (pintype "bidirectional"))
      (node (ref "LED34") (pin "6") (pinfunction "GREEN_C_6") (pintype "bidirectional"))
      (node (ref "LED35") (pin "4") (pinfunction "BLUE_C_4") (pintype "bidirectional"))
      (node (ref "LED35") (pin "5") (pinfunction "RED_C_5") (pintype "bidirectional"))
      (node (ref "LED35") (pin "6") (pinfunction "GREEN_C_6") (pintype "bidirectional"))
    )
    (net (code "37") (name "ROW6") (class "Default")
      (node (ref "IC2") (pin "17") (pinfunction "OUT2_17") (pintype "open_collector"))
      (node (ref "LED36") (pin "4") (pinfunction "BLUE_C_4") (pintype "bidirectional"))
      (node (ref "LED36") (pin "5") (pinfunction "RED_C_5") (pintype "bidirectional"))
      (node (ref "LED36") (pin "6") (pinfunction "GREEN_C_6") (pintype "bidirectional"))
      (node (ref "LED37") (pin "4") (pinfunction "BLUE_C_4") (pintype "bidirectional"))
      (node (ref "LED37") (pin "5") (pinfunction "RED_C_5") (pintype "bidirectional"))
      (node (ref "LED37") (pin "6") (pinfunction "GREEN_C_6") (pintype "bidirectional"))
      (node (ref "LED38") (pin "4") (pinfunction "BLUE_C_4") (pintype "bidirectional"))
      (node (ref "LED38") (pin "5") (pinfunction "RED_C_5") (pintype "bidirectional"))
      (node (ref "LED38") (pin "6") (pinfunction "GREEN_C_6") (pintype "bidirectional"))
      (node (ref "LED39") (pin "4") (pinfunction "BLUE_C_4") (pintype "bidirectional"))
      (node (ref "LED39") (pin "5") (pinfunction "RED_C_5") (pintype "bidirectional"))
      (node (ref "LED39") (pin "6") (pinfunction "GREEN_C_6") (pintype "bidirectional"))
      (node (ref "LED40") (pin "4") (pinfunction "BLUE_C_4") (pintype "bidirectional"))
      (node (ref "LED40") (pin "5") (pinfunction "RED_C_5") (pintype "bidirectional"))
      (node (ref "LED40") (pin "6") (pinfunction "GREEN_C_6") (pintype "bidirectional"))
      (node (ref "LED41") (pin "4") (pinfunction "BLUE_C_4") (pintype "bidirectional"))
      (node (ref "LED41") (pin "5") (pinfunction "RED_C_5") (pintype "bidirectional"))
      (node (ref "LED41") (pin "6") (pinfunction "GREEN_C_6") (pintype "bidirectional"))
      (node (ref "LED42") (pin "4") (pinfunction "BLUE_C_4") (pintype "bidirectional"))
      (node (ref "LED42") (pin "5") (pinfunction "RED_C_5") (pintype "bidirectional"))
      (node (ref "LED42") (pin "6") (pinfunction "GREEN_C_6") (pintype "bidirectional"))
    )
    (net (code "38") (name "ROW7") (class "Default")
      (node (ref "IC2") (pin "18") (pinfunction "OUT1_18") (pintype "open_collector"))
      (node (ref "LED43") (pin "4") (pinfunction "BLUE_C_4") (pintype "bidirectional"))
      (node (ref "LED43") (pin "5") (pinfunction "RED_C_5") (pintype "bidirectional"))
      (node (ref "LED43") (pin "6") (pinfunction "GREEN_C_6") (pintype "bidirectional"))
      (node (ref "LED44") (pin "4") (pinfunction "BLUE_C_4") (pintype "bidirectional"))
      (node (ref "LED44") (pin "5") (pinfunction "RED_C_5") (pintype "bidirectional"))
      (node (ref "LED44") (pin "6") (pinfunction "GREEN_C_6") (pintype "bidirectional"))
      (node (ref "LED45") (pin "4") (pinfunction "BLUE_C_4") (pintype "bidirectional"))
      (node (ref "LED45") (pin "5") (pinfunction "RED_C_5") (pintype "bidirectional"))
      (node (ref "LED45") (pin "6") (pinfunction "GREEN_C_6") (pintype "bidirectional"))
      (node (ref "LED46") (pin "4") (pinfunction "BLUE_C_4") (pintype "bidirectional"))
      (node (ref "LED46") (pin "5") (pinfunction "RED_C_5") (pintype "bidirectional"))
      (node (ref "LED46") (pin "6") (pinfunction "GREEN_C_6") (pintype "bidirectional"))
      (node (ref "LED47") (pin "4") (pinfunction "BLUE_C_4") (pintype "bidirectional"))
      (node (ref "LED47") (pin "5") (pinfunction "RED_C_5") (pintype "bidirectional"))
      (node (ref "LED47") (pin "6") (pinfunction "GREEN_C_6") (pintype "bidirectional"))
      (node (ref "LED48") (pin "4") (pinfunction "BLUE_C_4") (pintype "bidirectional"))
      (node (ref "LED48") (pin "5") (pinfunction "RED_C_5") (pintype "bidirectional"))
      (node (ref "LED48") (pin "6") (pinfunction "GREEN_C_6") (pintype "bidirectional"))
      (node (ref "LED49") (pin "4") (pinfunction "BLUE_C_4") (pintype "bidirectional"))
      (node (ref "LED49") (pin "5") (pinfunction "RED_C_5") (pintype "bidirectional"))
      (node (ref "LED49") (pin "6") (pinfunction "GREEN_C_6") (pintype "bidirectional"))
    )
    (net (code "39") (name "SCK") (class "Default")
      (node (ref "IC1") (pin "11") (pinfunction "SCK_11") (pintype "input"))
      (node (ref "IC5") (pin "11") (pinfunction "SCK_11") (pintype "input"))
      (node (ref "X2") (pin "4") (pinfunction "4_4") (pintype "passive"))
      (node (ref "X3") (pin "4") (pinfunction "4_4") (pintype "passive"))
    )
    (net (code "40") (name "VCC") (class "Default")
      (node (ref "C1") (pin "+") (pinfunction "+_+") (pintype "passive"))
      (node (ref "C2") (pin "1") (pinfunction "1_1") (pintype "passive"))
      (node (ref "C6") (pin "2") (pinfunction "2_2") (pintype "passive"))
      (node (ref "C7") (pin "+") (pinfunction "+_+") (pintype "passive"))
      (node (ref "C8") (pin "1") (pinfunction "1_1") (pintype "passive"))
      (node (ref "IC3") (pin "5") (pinfunction "VIN_5") (pintype "input"))
      (node (ref "IC4") (pin "3") (pinfunction "VIN_3") (pintype "input"))
      (node (ref "X1") (pin "2") (pinfunction "KL_2") (pintype "passive"))
      (node (ref "X2") (pin "10") (pinfunction "10_10") (pintype "passive"))
      (node (ref "X3") (pin "10") (pinfunction "10_10") (pintype "passive"))
    )
    (net (code "41") (name "VCC_LED") (class "Default")
      (node (ref "C4") (pin "1") (pinfunction "1_1") (pintype "passive"))
      (node (ref "C5") (pin "+") (pinfunction "+_+") (pintype "passive"))
      (node (ref "IC2") (pin "10") (pinfunction "DIODE_10") (pintype "power_in"))
      (node (ref "IC6") (pin "9") (pinfunction "GND_9") (pintype "power_in"))
      (node (ref "L1") (pin "2") (pinfunction "2_2") (pintype "passive"))
      (node (ref "R2") (pin "2") (pinfunction "2_2") (pintype "passive"))
    )
    (net (code "42") (name "unconnected-(IC1A-QA-Pad15)") (class "Default")
      (node (ref "IC1") (pin "15") (pinfunction "QA_15") (pintype "tri_state"))
    )
    (net (code "43") (name "unconnected-(IC1A-SCL-Pad10)") (class "Default")
      (node (ref "IC1") (pin "10") (pinfunction "SCL_10") (pintype "input"))
    )
    (net (code "44") (name "unconnected-(IC2-IN8-Pad8)") (class "Default")
      (node (ref "IC2") (pin "8") (pinfunction "IN8_8") (pintype "input"))
    )
    (net (code "45") (name "unconnected-(IC2-OUT8-Pad11)") (class "Default")
      (node (ref "IC2") (pin "11") (pinfunction "OUT8_11") (pintype "open_collector"))
    )
    (net (code "46") (name "unconnected-(IC5A-QA-Pad15)") (class "Default")
      (node (ref "IC5") (pin "15") (pinfunction "QA_15") (pintype "tri_state"))
    )
    (net (code "47") (name "unconnected-(IC5A-SCL-Pad10)") (class "Default")
      (node (ref "IC5") (pin "10") (pinfunction "SCL_10") (pintype "input"))
    )
    (net (code "48") (name "unconnected-(IC6-IN8-Pad8)") (class "Default")
      (node (ref "IC6") (pin "8") (pinfunction "IN8_8") (pintype "input"))
    )
    (net (code "49") (name "unconnected-(IC6-OUT8-Pad11)") (class "Default")
      (node (ref "IC6") (pin "11") (pinfunction "OUT8_11") (pintype "output"))
    )
    (net (code "50") (name "unconnected-(X2-Pad1)") (class "Default")
      (node (ref "X2") (pin "1") (pinfunction "1_1") (pintype "passive"))
    )
    (net (code "51") (name "unconnected-(X2-Pad2)") (class "Default")
      (node (ref "X2") (pin "2") (pinfunction "2_2") (pintype "passive"))
    )
    (net (code "52") (name "unconnected-(X2-Pad3)") (class "Default")
      (node (ref "X2") (pin "3") (pinfunction "3_3") (pintype "passive"))
    )
    (net (code "53") (name "unconnected-(X2-Pad7)") (class "Default")
      (node (ref "X2") (pin "7") (pinfunction "7_7") (pintype "passive"))
    )
    (net (code "54") (name "unconnected-(X2-Pad8)") (class "Default")
      (node (ref "X2") (pin "8") (pinfunction "8_8") (pintype "passive"))
    )
    (net (code "55") (name "unconnected-(X3-Pad1)") (class "Default")
      (node (ref "X3") (pin "1") (pinfunction "1_1") (pintype "passive"))
    )
    (net (code "56") (name "unconnected-(X3-Pad2)") (class "Default")
      (node (ref "X3") (pin "2") (pinfunction "2_2") (pintype "passive"))
    )
    (net (code "57") (name "unconnected-(X3-Pad3)") (class "Default")
      (node (ref "X3") (pin "3") (pinfunction "3_3") (pintype "passive"))
    )
    (net (code "58") (name "unconnected-(X3-Pad7)") (class "Default")
      (node (ref "X3") (pin "7") (pinfunction "7_7") (pintype "passive"))
    )
    (net (code "59") (name "unconnected-(X3-Pad8)") (class "Default")
      (node (ref "X3") (pin "8") (pinfunction "8_8") (pintype "passive"))
    )
  )
)
